# IO.net
KiCad netlist of a schematic drawn in Altium Designer
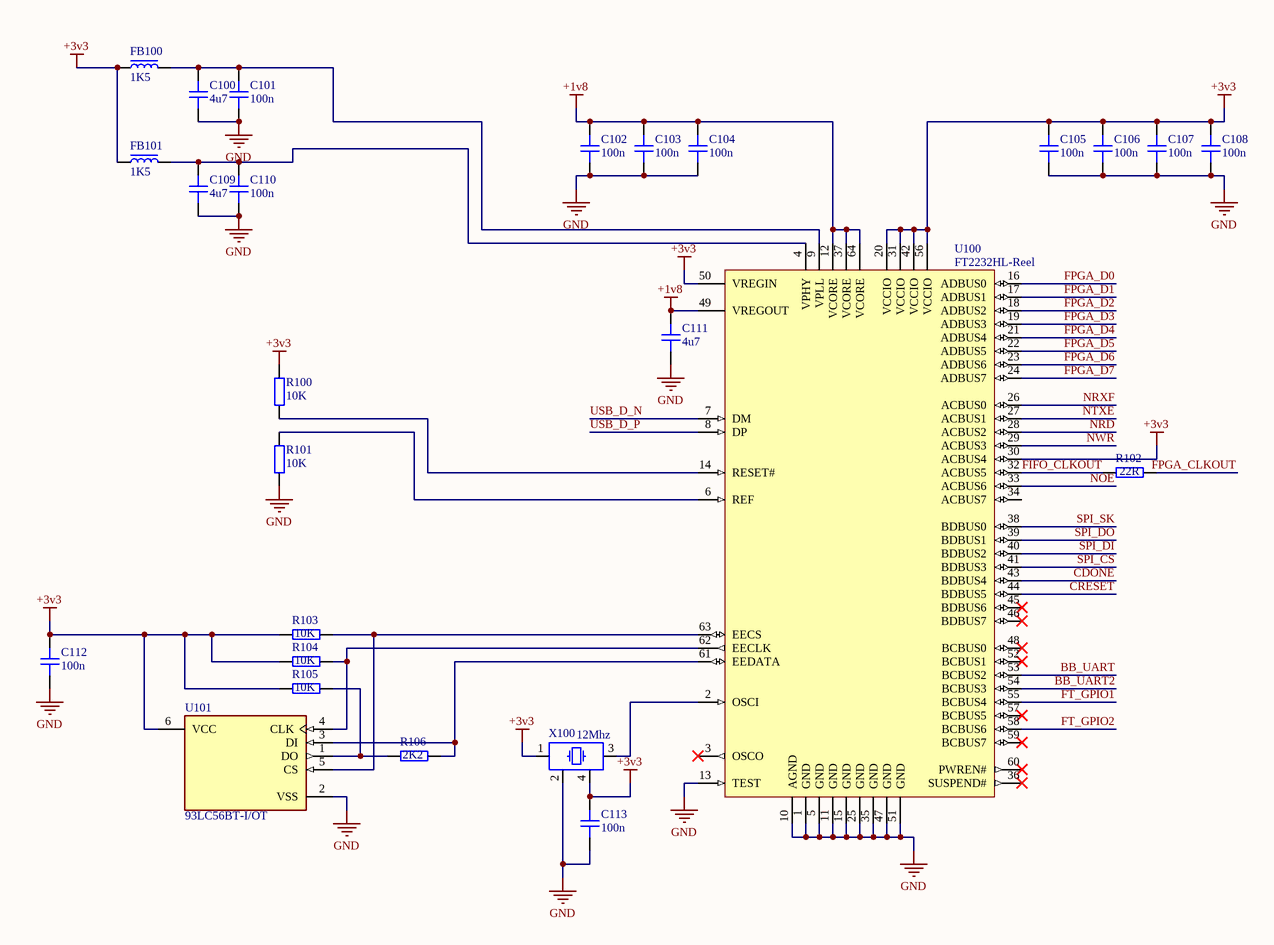
[diagram p0: IO.SchDoc]

(export (version "E")
  (design (tool "Eeschema 10.0.6"))
  (components
    (comp (ref "C100")
      (value "4u7")
      (footprint "CAP_0402")
      (description "Capacitor SMD 0402")
      (fields (field (name "MANUFACTURER PART NUMBER") "GRM155R61E475ME15D"))
      (libsource (lib "Schematic-Lib-PhilsLab") (part "CAP_0402"))
    )
    (comp (ref "C101")
      (value "100n")
      (footprint "CAP_0402")
      (description "Capacitor SMD 0402")
      (fields (field (name "MANUFACTURER PART NUMBER") "CL05B104KO5NNNC"))
      (libsource (lib "Schematic-Lib-PhilsLab") (part "CAP_0402"))
    )
    (comp (ref "C102")
      (value "100n")
      (footprint "CAP_0402")
      (description "Capacitor SMD 0402")
      (fields (field (name "MANUFACTURER PART NUMBER") "CL05B104KO5NNNC"))
      (libsource (lib "Schematic-Lib-PhilsLab") (part "CAP_0402"))
    )
    (comp (ref "C103")
      (value "100n")
      (footprint "CAP_0402")
      (description "Capacitor SMD 0402")
      (fields (field (name "MANUFACTURER PART NUMBER") "CL05B104KO5NNNC"))
      (libsource (lib "Schematic-Lib-PhilsLab") (part "CAP_0402"))
    )
    (comp (ref "C104")
      (value "100n")
      (footprint "CAP_0402")
      (description "Capacitor SMD 0402")
      (fields (field (name "MANUFACTURER PART NUMBER") "CL05B104KO5NNNC"))
      (libsource (lib "Schematic-Lib-PhilsLab") (part "CAP_0402"))
    )
    (comp (ref "C105")
      (value "100n")
      (footprint "CAP_0402")
      (description "Capacitor SMD 0402")
      (fields (field (name "MANUFACTURER PART NUMBER") "CL05B104KO5NNNC"))
      (libsource (lib "Schematic-Lib-PhilsLab") (part "CAP_0402"))
    )
    (comp (ref "C106")
      (value "100n")
      (footprint "CAP_0402")
      (description "Capacitor SMD 0402")
      (fields (field (name "MANUFACTURER PART NUMBER") "CL05B104KO5NNNC"))
      (libsource (lib "Schematic-Lib-PhilsLab") (part "CAP_0402"))
    )
    (comp (ref "C107")
      (value "100n")
      (footprint "CAP_0402")
      (description "Capacitor SMD 0402")
      (fields (field (name "MANUFACTURER PART NUMBER") "CL05B104KO5NNNC"))
      (libsource (lib "Schematic-Lib-PhilsLab") (part "CAP_0402"))
    )
    (comp (ref "C108")
      (value "100n")
      (footprint "CAP_0402")
      (description "Capacitor SMD 0402")
      (fields (field (name "MANUFACTURER PART NUMBER") "CL05B104KO5NNNC"))
      (libsource (lib "Schematic-Lib-PhilsLab") (part "CAP_0402"))
    )
    (comp (ref "C109")
      (value "4u7")
      (footprint "CAP_0402")
      (description "Capacitor SMD 0402")
      (fields (field (name "MANUFACTURER PART NUMBER") "GRM155R61E475ME15D"))
      (libsource (lib "Schematic-Lib-PhilsLab") (part "CAP_0402"))
    )
    (comp (ref "C110")
      (value "100n")
      (footprint "CAP_0402")
      (description "Capacitor SMD 0402")
      (fields (field (name "MANUFACTURER PART NUMBER") "CL05B104KO5NNNC"))
      (libsource (lib "Schematic-Lib-PhilsLab") (part "CAP_0402"))
    )
    (comp (ref "C111")
      (value "4u7")
      (footprint "CAP_0402")
      (description "Capacitor SMD 0402")
      (fields (field (name "MANUFACTURER PART NUMBER") "GRM155R61E475ME15D"))
      (libsource (lib "Schematic-Lib-PhilsLab") (part "CAP_0402"))
    )
    (comp (ref "C112")
      (value "100n")
      (footprint "CAP_0402")
      (description "Capacitor SMD 0402")
      (fields (field (name "MANUFACTURER PART NUMBER") "CL05B104KO5NNNC"))
      (libsource (lib "Schematic-Lib-PhilsLab") (part "CAP_0402"))
    )
    (comp (ref "C113")
      (value "100n")
      (footprint "CAP_0402")
      (description "Capacitor SMD 0402")
      (fields (field (name "MANUFACTURER PART NUMBER") "CL05B104KO5NNNC"))
      (libsource (lib "Schematic-Lib-PhilsLab") (part "CAP_0402"))
    )
    (comp (ref "FB100")
      (value "1K5")
      (footprint "FB_0603")
      (description "Ferrite Bead SMD 0603")
      (fields (field (name "MANUFACTURER PART NUMBER") "BLM18HE152SN1D"))
      (libsource (lib "Schematic-Lib-PhilsLab") (part "FB_0603"))
    )
    (comp (ref "FB101")
      (value "1K5")
      (footprint "FB_0603")
      (description "Ferrite Bead SMD 0603")
      (fields (field (name "MANUFACTURER PART NUMBER") "BLM18HE152SN1D"))
      (libsource (lib "Schematic-Lib-PhilsLab") (part "FB_0603"))
    )
    (comp (ref "R100")
      (value "10K")
      (footprint "RES_0402")
      (description "Resistor SMD 0402")
      (fields (field (name "MANUFACTURER PART NUMBER") "0402WGF1002TCE"))
      (libsource (lib "Schematic-Lib-PhilsLab") (part "RES_0402"))
    )
    (comp (ref "R101")
      (value "10K")
      (footprint "RES_0402")
      (description "Resistor SMD 0402")
      (fields (field (name "MANUFACTURER PART NUMBER") "0402WGF1002TCE"))
      (libsource (lib "Schematic-Lib-PhilsLab") (part "RES_0402"))
    )
    (comp (ref "R102")
      (value "22R")
      (footprint "RES_0402")
      (description "Resistor SMD 0402")
      (fields (field (name "MANUFACTURER PART NUMBER") "0402WGF220JTCE"))
      (libsource (lib "Schematic-Lib-PhilsLab") (part "RES_0402"))
    )
    (comp (ref "R103")
      (value "10K")
      (footprint "RES_0402")
      (description "Resistor SMD 0402")
      (fields (field (name "MANUFACTURER PART NUMBER") "0402WGF1002TCE"))
      (libsource (lib "Schematic-Lib-PhilsLab") (part "RES_0402"))
    )
    (comp (ref "R104")
      (value "10K")
      (footprint "RES_0402")
      (description "Resistor SMD 0402")
      (fields (field (name "MANUFACTURER PART NUMBER") "0402WGF1002TCE"))
      (libsource (lib "Schematic-Lib-PhilsLab") (part "RES_0402"))
    )
    (comp (ref "R105")
      (value "10K")
      (footprint "RES_0402")
      (description "Resistor SMD 0402")
      (fields (field (name "MANUFACTURER PART NUMBER") "0402WGF1002TCE"))
      (libsource (lib "Schematic-Lib-PhilsLab") (part "RES_0402"))
    )
    (comp (ref "R106")
      (value "2K2")
      (footprint "RES_0402")
      (description "Resistor SMD 0402")
      (fields (field (name "MANUFACTURER PART NUMBER") "0402WGF2201TCE"))
      (libsource (lib "Schematic-Lib-PhilsLab") (part "RES_0402"))
    )
    (comp (ref "U100")
      (value "FT2232HL-Reel")
      (footprint "LQFP-64_M")
      (description "Dual High Speed USB To Multipurpose UART/FIFO IC, 64-pin LQFP, Tape and Reel")
      (fields (field (name "MANUFACTURER") "FTDI"))
      (libsource (lib "Altium Content Vault") (part "COM-UART-FT2232H-LQFP64"))
    )
    (comp (ref "U101")
      (value "93LC56BT-I/OT")
      (footprint "FP-C04-028-MFG")
      (description "IC EEPROM 2K SPI 2MHZ SOT23-6")
      (libsource (lib "Altium Content Vault") (part "dc1ae428e19de5f6f67d4f5eaa7d586"))
    )
    (comp (ref "X100")
      (value "12Mhz")
      (footprint "XTAL_2520")
      (description "Crystal SMD 2520")
      (fields (field (name "MANUFACTURER PART NUMBER") "SX2M12.000B10F20TNN"))
      (libsource (lib "Schematic-Lib-PhilsLab") (part "XTAL_2520"))
    )
  )
  (nets
    (net (code "1") (name "+1v8") (class "Default")
      (node (ref "C102") (pin "2") (pinfunction "2_2") (pintype "passive"))
      (node (ref "C103") (pin "2") (pinfunction "2_2") (pintype "passive"))
      (node (ref "C104") (pin "2") (pinfunction "2_2") (pintype "passive"))
      (node (ref "C111") (pin "2") (pinfunction "2_2") (pintype "passive"))
      (node (ref "U100") (pin "12") (pinfunction "VCORE_12") (pintype "power_in"))
      (node (ref "U100") (pin "37") (pinfunction "VCORE_37") (pintype "power_in"))
      (node (ref "U100") (pin "49") (pinfunction "VREGOUT_49") (pintype "power_in"))
      (node (ref "U100") (pin "64") (pinfunction "VCORE_64") (pintype "power_in"))
    )
    (net (code "2") (name "+3v3") (class "Default")
      (node (ref "C105") (pin "2") (pinfunction "2_2") (pintype "passive"))
      (node (ref "C106") (pin "2") (pinfunction "2_2") (pintype "passive"))
      (node (ref "C107") (pin "2") (pinfunction "2_2") (pintype "passive"))
      (node (ref "C108") (pin "2") (pinfunction "2_2") (pintype "passive"))
      (node (ref "C112") (pin "2") (pinfunction "2_2") (pintype "passive"))
      (node (ref "C113") (pin "2") (pinfunction "2_2") (pintype "passive"))
      (node (ref "FB100") (pin "1") (pinfunction "1_1") (pintype "passive"))
      (node (ref "FB101") (pin "1") (pinfunction "1_1") (pintype "passive"))
      (node (ref "R100") (pin "2") (pinfunction "2_2") (pintype "passive"))
      (node (ref "R103") (pin "1") (pinfunction "1_1") (pintype "passive"))
      (node (ref "R104") (pin "1") (pinfunction "1_1") (pintype "passive"))
      (node (ref "R105") (pin "1") (pinfunction "1_1") (pintype "passive"))
      (node (ref "U100") (pin "20") (pinfunction "VCCIO_20") (pintype "power_in"))
      (node (ref "U100") (pin "30") (pinfunction "ACBUS4_30") (pintype "bidirectional"))
      (node (ref "U100") (pin "31") (pinfunction "VCCIO_31") (pintype "power_in"))
      (node (ref "U100") (pin "42") (pinfunction "VCCIO_42") (pintype "power_in"))
      (node (ref "U100") (pin "50") (pinfunction "VREGIN_50") (pintype "power_in"))
      (node (ref "U100") (pin "56") (pinfunction "VCCIO_56") (pintype "power_in"))
      (node (ref "U101") (pin "6") (pinfunction "VCC_6") (pintype "power_in"))
      (node (ref "X100") (pin "1") (pinfunction "1_1") (pintype "passive"))
      (node (ref "X100") (pin "4") (pinfunction "4_4") (pintype "passive"))
    )
    (net (code "3") (name "/BB_UART") (class "Default")
      (node (ref "U100") (pin "53") (pinfunction "BCBUS2_53") (pintype "bidirectional"))
    )
    (net (code "4") (name "/BB_UART2") (class "Default")
      (node (ref "U100") (pin "54") (pinfunction "BCBUS3_54") (pintype "bidirectional"))
    )
    (net (code "5") (name "/CDONE") (class "Default")
      (node (ref "U100") (pin "43") (pinfunction "BDBUS4_43") (pintype "bidirectional"))
    )
    (net (code "6") (name "/CRESET") (class "Default")
      (node (ref "U100") (pin "44") (pinfunction "BDBUS5_44") (pintype "bidirectional"))
    )
    (net (code "7") (name "/FIFO_CLKOUT") (class "Default")
      (node (ref "R102") (pin "1") (pinfunction "1_1") (pintype "passive"))
      (node (ref "U100") (pin "32") (pinfunction "ACBUS5_32") (pintype "bidirectional"))
    )
    (net (code "8") (name "/FPGA_CLKOUT") (class "Default")
      (node (ref "R102") (pin "2") (pinfunction "2_2") (pintype "passive"))
    )
    (net (code "9") (name "/FPGA_D0") (class "Default")
      (node (ref "U100") (pin "16") (pinfunction "ADBUS0_16") (pintype "bidirectional"))
    )
    (net (code "10") (name "/FPGA_D1") (class "Default")
      (node (ref "U100") (pin "17") (pinfunction "ADBUS1_17") (pintype "bidirectional"))
    )
    (net (code "11") (name "/FPGA_D2") (class "Default")
      (node (ref "U100") (pin "18") (pinfunction "ADBUS2_18") (pintype "bidirectional"))
    )
    (net (code "12") (name "/FPGA_D3") (class "Default")
      (node (ref "U100") (pin "19") (pinfunction "ADBUS3_19") (pintype "bidirectional"))
    )
    (net (code "13") (name "/FPGA_D4") (class "Default")
      (node (ref "U100") (pin "21") (pinfunction "ADBUS4_21") (pintype "bidirectional"))
    )
    (net (code "14") (name "/FPGA_D5") (class "Default")
      (node (ref "U100") (pin "22") (pinfunction "ADBUS5_22") (pintype "bidirectional"))
    )
    (net (code "15") (name "/FPGA_D6") (class "Default")
      (node (ref "U100") (pin "23") (pinfunction "ADBUS6_23") (pintype "bidirectional"))
    )
    (net (code "16") (name "/FPGA_D7") (class "Default")
      (node (ref "U100") (pin "24") (pinfunction "ADBUS7_24") (pintype "bidirectional"))
    )
    (net (code "17") (name "/FT_GPIO1") (class "Default")
      (node (ref "U100") (pin "55") (pinfunction "BCBUS4_55") (pintype "bidirectional"))
    )
    (net (code "18") (name "/FT_GPIO2") (class "Default")
      (node (ref "U100") (pin "58") (pinfunction "BCBUS6_58") (pintype "bidirectional"))
    )
    (net (code "19") (name "/NOE") (class "Default")
      (node (ref "U100") (pin "33") (pinfunction "ACBUS6_33") (pintype "bidirectional"))
    )
    (net (code "20") (name "/NRD") (class "Default")
      (node (ref "U100") (pin "28") (pinfunction "ACBUS2_28") (pintype "bidirectional"))
    )
    (net (code "21") (name "/NRXF") (class "Default")
      (node (ref "U100") (pin "26") (pinfunction "ACBUS0_26") (pintype "bidirectional"))
    )
    (net (code "22") (name "/NTXE") (class "Default")
      (node (ref "U100") (pin "27") (pinfunction "ACBUS1_27") (pintype "bidirectional"))
    )
    (net (code "23") (name "/NWR") (class "Default")
      (node (ref "U100") (pin "29") (pinfunction "ACBUS3_29") (pintype "bidirectional"))
    )
    (net (code "24") (name "/SPI_CS") (class "Default")
      (node (ref "U100") (pin "41") (pinfunction "BDBUS3_41") (pintype "bidirectional"))
    )
    (net (code "25") (name "/SPI_DI") (class "Default")
      (node (ref "U100") (pin "40") (pinfunction "BDBUS2_40") (pintype "bidirectional"))
    )
    (net (code "26") (name "/SPI_DO") (class "Default")
      (node (ref "U100") (pin "39") (pinfunction "BDBUS1_39") (pintype "bidirectional"))
    )
    (net (code "27") (name "/SPI_SK") (class "Default")
      (node (ref "U100") (pin "38") (pinfunction "BDBUS0_38") (pintype "bidirectional"))
    )
    (net (code "28") (name "/USB_D_N") (class "Default")
      (node (ref "U100") (pin "7") (pinfunction "DM_7") (pintype "input"))
    )
    (net (code "29") (name "/USB_D_P") (class "Default")
      (node (ref "U100") (pin "8") (pinfunction "DP_8") (pintype "input"))
    )
    (net (code "30") (name "GND") (class "Default")
      (node (ref "C100") (pin "1") (pinfunction "1_1") (pintype "passive"))
      (node (ref "C101") (pin "1") (pinfunction "1_1") (pintype "passive"))
      (node (ref "C102") (pin "1") (pinfunction "1_1") (pintype "passive"))
      (node (ref "C103") (pin "1") (pinfunction "1_1") (pintype "passive"))
      (node (ref "C104") (pin "1") (pinfunction "1_1") (pintype "passive"))
      (node (ref "C105") (pin "1") (pinfunction "1_1") (pintype "passive"))
      (node (ref "C106") (pin "1") (pinfunction "1_1") (pintype "passive"))
      (node (ref "C107") (pin "1") (pinfunction "1_1") (pintype "passive"))
      (node (ref "C108") (pin "1") (pinfunction "1_1") (pintype "passive"))
      (node (ref "C109") (pin "1") (pinfunction "1_1") (pintype "passive"))
      (node (ref "C110") (pin "1") (pinfunction "1_1") (pintype "passive"))
      (node (ref "C111") (pin "1") (pinfunction "1_1") (pintype "passive"))
      (node (ref "C112") (pin "1") (pinfunction "1_1") (pintype "passive"))
      (node (ref "C113") (pin "1") (pinfunction "1_1") (pintype "passive"))
      (node (ref "R101") (pin "2") (pinfunction "2_2") (pintype "passive"))
      (node (ref "U100") (pin "1") (pinfunction "GND_1") (pintype "power_in"))
      (node (ref "U100") (pin "10") (pinfunction "AGND_10") (pintype "power_in"))
      (node (ref "U100") (pin "11") (pinfunction "GND_11") (pintype "power_in"))
      (node (ref "U100") (pin "13") (pinfunction "TEST_13") (pintype "input"))
      (node (ref "U100") (pin "15") (pinfunction "GND_15") (pintype "power_in"))
      (node (ref "U100") (pin "25") (pinfunction "GND_25") (pintype "power_in"))
      (node (ref "U100") (pin "35") (pinfunction "GND_35") (pintype "power_in"))
      (node (ref "U100") (pin "47") (pinfunction "GND_47") (pintype "power_in"))
      (node (ref "U100") (pin "5") (pinfunction "GND_5") (pintype "power_in"))
      (node (ref "U100") (pin "51") (pinfunction "GND_51") (pintype "power_in"))
      (node (ref "U101") (pin "2") (pinfunction "VSS_2") (pintype "power_in"))
      (node (ref "X100") (pin "2") (pinfunction "2_2") (pintype "passive"))
    )
    (net (code "31") (name "Net-(U100-EECLK)") (class "Default")
      (node (ref "R104") (pin "2") (pinfunction "2_2") (pintype "passive"))
      (node (ref "U100") (pin "62") (pinfunction "EECLK_62") (pintype "output"))
      (node (ref "U101") (pin "4") (pinfunction "CLK_4") (pintype "input"))
    )
    (net (code "32") (name "Net-(U100-EECS)") (class "Default")
      (node (ref "R103") (pin "2") (pinfunction "2_2") (pintype "passive"))
      (node (ref "U100") (pin "63") (pinfunction "EECS_63") (pintype "bidirectional"))
      (node (ref "U101") (pin "5") (pinfunction "CS_5") (pintype "input"))
    )
    (net (code "33") (name "Net-(U100-EEDATA)") (class "Default")
      (node (ref "R106") (pin "2") (pinfunction "2_2") (pintype "passive"))
      (node (ref "U100") (pin "61") (pinfunction "EEDATA_61") (pintype "bidirectional"))
      (node (ref "U101") (pin "3") (pinfunction "DI_3") (pintype "input"))
    )
    (net (code "34") (name "Net-(U100-OSCI)") (class "Default")
      (node (ref "U100") (pin "2") (pinfunction "OSCI_2") (pintype "input"))
      (node (ref "X100") (pin "3") (pinfunction "3_3") (pintype "passive"))
    )
    (net (code "35") (name "Net-(U100-REF)") (class "Default")
      (node (ref "R101") (pin "1") (pinfunction "1_1") (pintype "passive"))
      (node (ref "U100") (pin "6") (pinfunction "REF_6") (pintype "input"))
    )
    (net (code "36") (name "Net-(U100-RESET#)") (class "Default")
      (node (ref "R100") (pin "1") (pinfunction "1_1") (pintype "passive"))
      (node (ref "U100") (pin "14") (pinfunction "RESET#_14") (pintype "input"))
    )
    (net (code "37") (name "Net-(U100-VPHY)") (class "Default")
      (node (ref "C109") (pin "2") (pinfunction "2_2") (pintype "passive"))
      (node (ref "C110") (pin "2") (pinfunction "2_2") (pintype "passive"))
      (node (ref "FB101") (pin "2") (pinfunction "2_2") (pintype "passive"))
      (node (ref "U100") (pin "4") (pinfunction "VPHY_4") (pintype "power_in"))
    )
    (net (code "38") (name "Net-(U100-VPLL)") (class "Default")
      (node (ref "C100") (pin "2") (pinfunction "2_2") (pintype "passive"))
      (node (ref "C101") (pin "2") (pinfunction "2_2") (pintype "passive"))
      (node (ref "FB100") (pin "2") (pinfunction "2_2") (pintype "passive"))
      (node (ref "U100") (pin "9") (pinfunction "VPLL_9") (pintype "power_in"))
    )
    (net (code "39") (name "Net-(U101-DO)") (class "Default")
      (node (ref "R105") (pin "2") (pinfunction "2_2") (pintype "passive"))
      (node (ref "R106") (pin "1") (pinfunction "1_1") (pintype "passive"))
      (node (ref "U101") (pin "1") (pinfunction "DO_1") (pintype "output"))
    )
    (net (code "40") (name "unconnected-(U100-ACBUS7-Pad34)") (class "Default")
      (node (ref "U100") (pin "34") (pinfunction "ACBUS7_34") (pintype "bidirectional"))
    )
    (net (code "41") (name "unconnected-(U100-BCBUS0-Pad48)") (class "Default")
      (node (ref "U100") (pin "48") (pinfunction "BCBUS0_48") (pintype "bidirectional+no_connect"))
    )
    (net (code "42") (name "unconnected-(U100-BCBUS1-Pad52)") (class "Default")
      (node (ref "U100") (pin "52") (pinfunction "BCBUS1_52") (pintype "bidirectional+no_connect"))
    )
    (net (code "43") (name "unconnected-(U100-BCBUS5-Pad57)") (class "Default")
      (node (ref "U100") (pin "57") (pinfunction "BCBUS5_57") (pintype "bidirectional+no_connect"))
    )
    (net (code "44") (name "unconnected-(U100-BCBUS7-Pad59)") (class "Default")
      (node (ref "U100") (pin "59") (pinfunction "BCBUS7_59") (pintype "bidirectional+no_connect"))
    )
    (net (code "45") (name "unconnected-(U100-BDBUS6-Pad45)") (class "Default")
      (node (ref "U100") (pin "45") (pinfunction "BDBUS6_45") (pintype "bidirectional+no_connect"))
    )
    (net (code "46") (name "unconnected-(U100-BDBUS7-Pad46)") (class "Default")
      (node (ref "U100") (pin "46") (pinfunction "BDBUS7_46") (pintype "bidirectional+no_connect"))
    )
    (net (code "47") (name "unconnected-(U100-OSCO-Pad3)") (class "Default")
      (node (ref "U100") (pin "3") (pinfunction "OSCO_3") (pintype "output+no_connect"))
    )
    (net (code "48") (name "unconnected-(U100-PWREN#-Pad60)") (class "Default")
      (node (ref "U100") (pin "60") (pinfunction "PWREN#_60") (pintype "output+no_connect"))
    )
    (net (code "49") (name "unconnected-(U100-SUSPEND#-Pad36)") (class "Default")
      (node (ref "U100") (pin "36") (pinfunction "SUSPEND#_36") (pintype "output+no_connect"))
    )
  )
)
